# demo_46k22.net
KiCad netlist of a schematic drawn in EAGLE
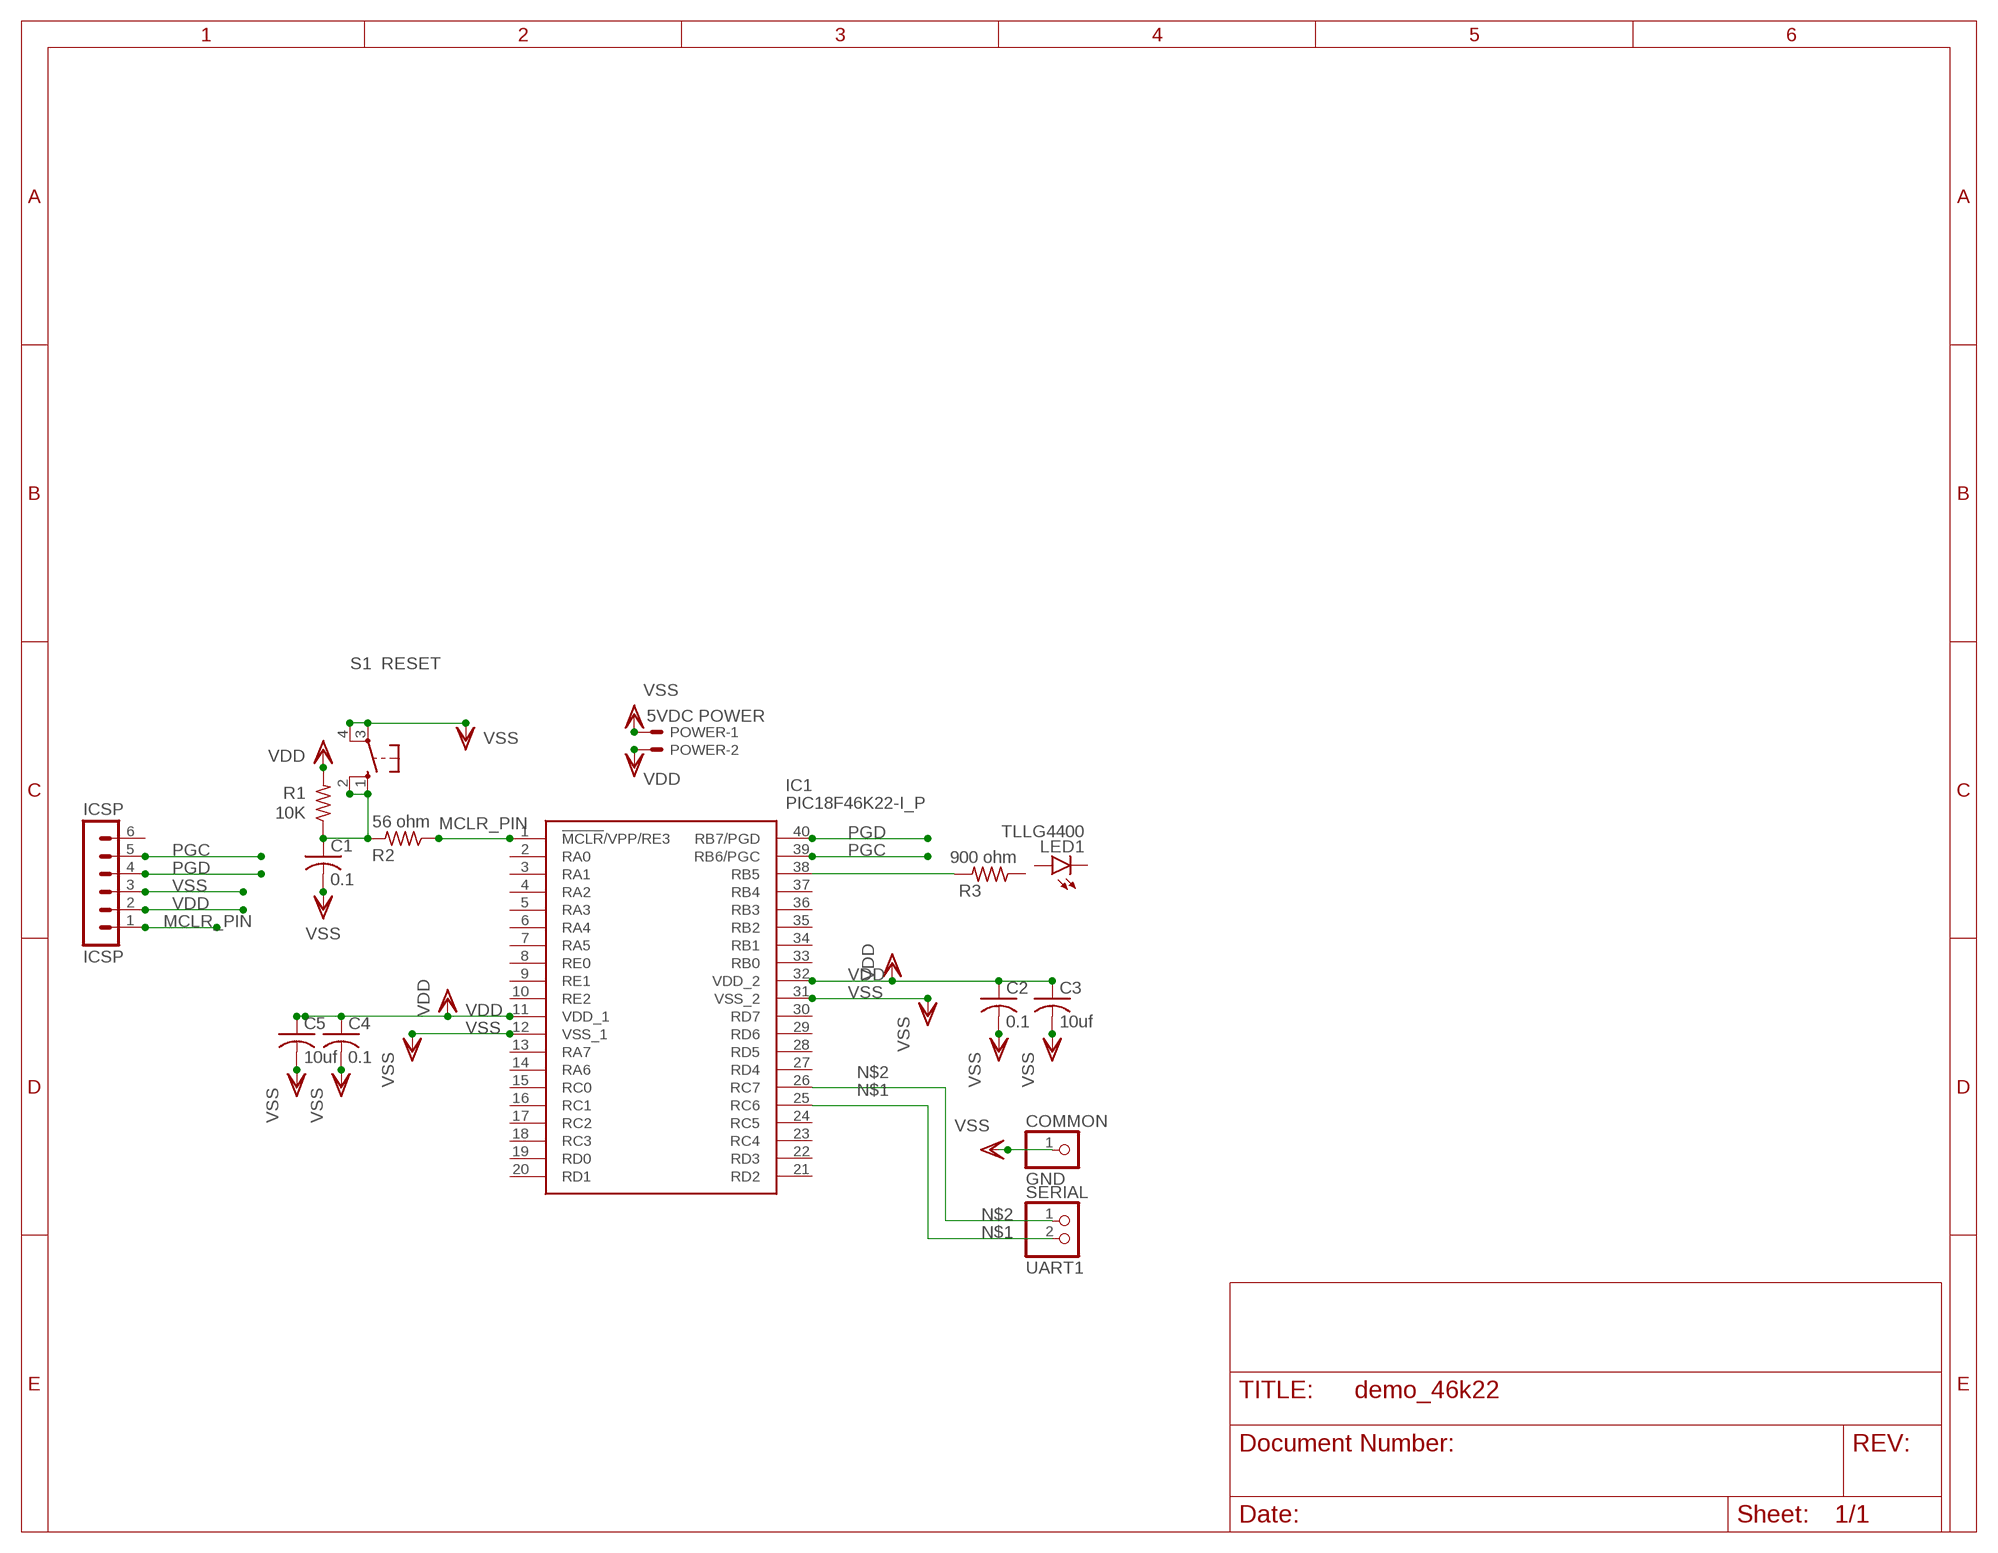
[diagram p0: schematic, sheet 1]

(export (version "E")
  (design (tool "Eeschema 10.0.6"))
  (components
    (comp (ref "C1")
      (value "0.1")
      (footprint "eagle-import:C025-030X050")
      (libsource (lib "eagle-import") (part "C-US025-030X050"))
    )
    (comp (ref "C2")
      (value "0.1")
      (footprint "eagle-import:C025-030X050")
      (libsource (lib "eagle-import") (part "C-US025-030X050"))
    )
    (comp (ref "C3")
      (value "10uf")
      (footprint "eagle-import:C025-030X050")
      (libsource (lib "eagle-import") (part "C-US025-030X050"))
    )
    (comp (ref "C4")
      (value "0.1")
      (footprint "eagle-import:C025-030X050")
      (libsource (lib "eagle-import") (part "C-US025-030X050"))
    )
    (comp (ref "C5")
      (value "10uf")
      (footprint "eagle-import:C025-030X050")
      (libsource (lib "eagle-import") (part "C-US025-030X050"))
    )
    (comp (ref "COMMON")
      (value "GND")
      (footprint "eagle-import:1X01")
      (libsource (lib "eagle-import") (part "PINHD-1X1"))
    )
    (comp (ref "IC1")
      (value "PIC18F46K22-I_P")
      (footprint "eagle-import:DIP1543W58P254L5175H635Q40N")
      (fields
        (field (name "MANUFACTURER_PART_NUMBER") "PIC18F46K22-I/P")
        (field (name "MOUSER_PART_NUMBER") "579-PIC18F46K22IP")
      )
      (libsource (lib "eagle-import") (part "PIC18F46K22-I_P"))
    )
    (comp (ref "ICSP")
      (value "ICSP")
      (footprint "eagle-import:MA06-1")
      (libsource (lib "eagle-import") (part "MA06-1"))
    )
    (comp (ref "LED1")
      (value "TLLG4400")
      (footprint "eagle-import:LED3MM")
      (fields (field (name "MF") "VISHAY SEMICONDUCTOR"))
      (libsource (lib "eagle-import") (part "TLLG4400"))
    )
    (comp (ref "POWER")
      (value "5VDC POWER")
      (footprint "eagle-import:22-23-2021")
      (fields (field (name "MF") "MOLEX") (field (name "MPN") "22-23-2021"))
      (libsource (lib "eagle-import") (part "22-23-2021"))
    )
    (comp (ref "R1")
      (value "10K")
      (footprint "eagle-import:0204_7")
      (libsource (lib "eagle-import") (part "R-US_0204/7"))
    )
    (comp (ref "R2")
      (value "56 ohm")
      (footprint "eagle-import:0204_7")
      (libsource (lib "eagle-import") (part "R-US_0204/7"))
    )
    (comp (ref "R3")
      (value "900 ohm")
      (footprint "eagle-import:0204_7")
      (libsource (lib "eagle-import") (part "R-US_0204/7"))
    )
    (comp (ref "S1")
      (value "RESET")
      (footprint "eagle-import:B3F-10XX")
      (fields (field (name "MPN") "B3F-1000"))
      (libsource (lib "eagle-import") (part "10-XX"))
    )
    (comp (ref "SERIAL")
      (value "UART1")
      (footprint "eagle-import:1X02")
      (libsource (lib "eagle-import") (part "PINHD-1X2"))
    )
  )
  (nets
    (net (code "1") (name "/MCLR_PIN") (class "Default")
      (node (ref "IC1") (pin "1") (pinfunction "~{MCLR}/VPP/RE3_1") (pintype "bidirectional"))
      (node (ref "ICSP") (pin "1") (pinfunction "1_1") (pintype "passive"))
      (node (ref "R2") (pin "1") (pinfunction "1_1") (pintype "passive"))
    )
    (net (code "2") (name "/N$1") (class "Default")
      (node (ref "IC1") (pin "25") (pinfunction "RC6_25") (pintype "bidirectional"))
      (node (ref "SERIAL") (pin "2") (pinfunction "2_2") (pintype "passive"))
    )
    (net (code "3") (name "/N$2") (class "Default")
      (node (ref "IC1") (pin "26") (pinfunction "RC7_26") (pintype "bidirectional"))
      (node (ref "SERIAL") (pin "1") (pinfunction "1_1") (pintype "passive"))
    )
    (net (code "4") (name "/PGC") (class "Default")
      (node (ref "IC1") (pin "39") (pinfunction "RB6/PGC_39") (pintype "bidirectional"))
      (node (ref "ICSP") (pin "5") (pinfunction "5_5") (pintype "passive"))
    )
    (net (code "5") (name "/PGD") (class "Default")
      (node (ref "IC1") (pin "40") (pinfunction "RB7/PGD_40") (pintype "bidirectional"))
      (node (ref "ICSP") (pin "4") (pinfunction "4_4") (pintype "passive"))
    )
    (net (code "6") (name "Net-(IC1-RB5)") (class "Default")
      (node (ref "IC1") (pin "38") (pinfunction "RB5_38") (pintype "bidirectional"))
      (node (ref "R3") (pin "2") (pinfunction "2_2") (pintype "passive"))
    )
    (net (code "7") (name "Net-(S1-S)") (class "Default")
      (node (ref "C1") (pin "1") (pinfunction "1_1") (pintype "passive"))
      (node (ref "R1") (pin "1") (pinfunction "1_1") (pintype "passive"))
      (node (ref "R2") (pin "2") (pinfunction "2_2") (pintype "passive"))
      (node (ref "S1") (pin "1") (pinfunction "S_1") (pintype "passive"))
      (node (ref "S1") (pin "2") (pinfunction "S1_2") (pintype "passive"))
    )
    (net (code "8") (name "VDD") (class "Default")
      (node (ref "C2") (pin "1") (pinfunction "1_1") (pintype "passive"))
      (node (ref "C3") (pin "1") (pinfunction "1_1") (pintype "passive"))
      (node (ref "C4") (pin "1") (pinfunction "1_1") (pintype "passive"))
      (node (ref "C5") (pin "1") (pinfunction "1_1") (pintype "passive"))
      (node (ref "IC1") (pin "11") (pinfunction "VDD_1_11") (pintype "bidirectional"))
      (node (ref "IC1") (pin "32") (pinfunction "VDD_2_32") (pintype "bidirectional"))
      (node (ref "ICSP") (pin "2") (pinfunction "2_2") (pintype "passive"))
      (node (ref "POWER") (pin "2") (pinfunction "S_2") (pintype "passive"))
      (node (ref "R1") (pin "2") (pinfunction "2_2") (pintype "passive"))
    )
    (net (code "9") (name "VSS") (class "Default")
      (node (ref "C1") (pin "2") (pinfunction "2_2") (pintype "passive"))
      (node (ref "C2") (pin "2") (pinfunction "2_2") (pintype "passive"))
      (node (ref "C3") (pin "2") (pinfunction "2_2") (pintype "passive"))
      (node (ref "C4") (pin "2") (pinfunction "2_2") (pintype "passive"))
      (node (ref "C5") (pin "2") (pinfunction "2_2") (pintype "passive"))
      (node (ref "COMMON") (pin "1") (pinfunction "1_1") (pintype "passive"))
      (node (ref "IC1") (pin "12") (pinfunction "VSS_1_12") (pintype "bidirectional"))
      (node (ref "IC1") (pin "31") (pinfunction "VSS_2_31") (pintype "bidirectional"))
      (node (ref "ICSP") (pin "3") (pinfunction "3_3") (pintype "passive"))
      (node (ref "POWER") (pin "1") (pinfunction "S_1") (pintype "passive"))
      (node (ref "S1") (pin "3") (pinfunction "P_3") (pintype "passive"))
      (node (ref "S1") (pin "4") (pinfunction "P1_4") (pintype "passive"))
    )
    (net (code "10") (name "unconnected-(IC1-RA0-Pad2)") (class "Default")
      (node (ref "IC1") (pin "2") (pinfunction "RA0_2") (pintype "bidirectional"))
    )
    (net (code "11") (name "unconnected-(IC1-RA1-Pad3)") (class "Default")
      (node (ref "IC1") (pin "3") (pinfunction "RA1_3") (pintype "bidirectional"))
    )
    (net (code "12") (name "unconnected-(IC1-RA2-Pad4)") (class "Default")
      (node (ref "IC1") (pin "4") (pinfunction "RA2_4") (pintype "bidirectional"))
    )
    (net (code "13") (name "unconnected-(IC1-RA3-Pad5)") (class "Default")
      (node (ref "IC1") (pin "5") (pinfunction "RA3_5") (pintype "bidirectional"))
    )
    (net (code "14") (name "unconnected-(IC1-RA4-Pad6)") (class "Default")
      (node (ref "IC1") (pin "6") (pinfunction "RA4_6") (pintype "bidirectional"))
    )
    (net (code "15") (name "unconnected-(IC1-RA5-Pad7)") (class "Default")
      (node (ref "IC1") (pin "7") (pinfunction "RA5_7") (pintype "bidirectional"))
    )
    (net (code "16") (name "unconnected-(IC1-RA6-Pad14)") (class "Default")
      (node (ref "IC1") (pin "14") (pinfunction "RA6_14") (pintype "bidirectional"))
    )
    (net (code "17") (name "unconnected-(IC1-RA7-Pad13)") (class "Default")
      (node (ref "IC1") (pin "13") (pinfunction "RA7_13") (pintype "bidirectional"))
    )
    (net (code "18") (name "unconnected-(IC1-RB0-Pad33)") (class "Default")
      (node (ref "IC1") (pin "33") (pinfunction "RB0_33") (pintype "bidirectional"))
    )
    (net (code "19") (name "unconnected-(IC1-RB1-Pad34)") (class "Default")
      (node (ref "IC1") (pin "34") (pinfunction "RB1_34") (pintype "bidirectional"))
    )
    (net (code "20") (name "unconnected-(IC1-RB2-Pad35)") (class "Default")
      (node (ref "IC1") (pin "35") (pinfunction "RB2_35") (pintype "bidirectional"))
    )
    (net (code "21") (name "unconnected-(IC1-RB3-Pad36)") (class "Default")
      (node (ref "IC1") (pin "36") (pinfunction "RB3_36") (pintype "bidirectional"))
    )
    (net (code "22") (name "unconnected-(IC1-RB4-Pad37)") (class "Default")
      (node (ref "IC1") (pin "37") (pinfunction "RB4_37") (pintype "bidirectional"))
    )
    (net (code "23") (name "unconnected-(IC1-RC0-Pad15)") (class "Default")
      (node (ref "IC1") (pin "15") (pinfunction "RC0_15") (pintype "bidirectional"))
    )
    (net (code "24") (name "unconnected-(IC1-RC1-Pad16)") (class "Default")
      (node (ref "IC1") (pin "16") (pinfunction "RC1_16") (pintype "bidirectional"))
    )
    (net (code "25") (name "unconnected-(IC1-RC2-Pad17)") (class "Default")
      (node (ref "IC1") (pin "17") (pinfunction "RC2_17") (pintype "bidirectional"))
    )
    (net (code "26") (name "unconnected-(IC1-RC3-Pad18)") (class "Default")
      (node (ref "IC1") (pin "18") (pinfunction "RC3_18") (pintype "bidirectional"))
    )
    (net (code "27") (name "unconnected-(IC1-RC4-Pad23)") (class "Default")
      (node (ref "IC1") (pin "23") (pinfunction "RC4_23") (pintype "bidirectional"))
    )
    (net (code "28") (name "unconnected-(IC1-RC5-Pad24)") (class "Default")
      (node (ref "IC1") (pin "24") (pinfunction "RC5_24") (pintype "bidirectional"))
    )
    (net (code "29") (name "unconnected-(IC1-RD0-Pad19)") (class "Default")
      (node (ref "IC1") (pin "19") (pinfunction "RD0_19") (pintype "bidirectional"))
    )
    (net (code "30") (name "unconnected-(IC1-RD1-Pad20)") (class "Default")
      (node (ref "IC1") (pin "20") (pinfunction "RD1_20") (pintype "bidirectional"))
    )
    (net (code "31") (name "unconnected-(IC1-RD2-Pad21)") (class "Default")
      (node (ref "IC1") (pin "21") (pinfunction "RD2_21") (pintype "bidirectional"))
    )
    (net (code "32") (name "unconnected-(IC1-RD3-Pad22)") (class "Default")
      (node (ref "IC1") (pin "22") (pinfunction "RD3_22") (pintype "bidirectional"))
    )
    (net (code "33") (name "unconnected-(IC1-RD4-Pad27)") (class "Default")
      (node (ref "IC1") (pin "27") (pinfunction "RD4_27") (pintype "bidirectional"))
    )
    (net (code "34") (name "unconnected-(IC1-RD5-Pad28)") (class "Default")
      (node (ref "IC1") (pin "28") (pinfunction "RD5_28") (pintype "bidirectional"))
    )
    (net (code "35") (name "unconnected-(IC1-RD6-Pad29)") (class "Default")
      (node (ref "IC1") (pin "29") (pinfunction "RD6_29") (pintype "bidirectional"))
    )
    (net (code "36") (name "unconnected-(IC1-RD7-Pad30)") (class "Default")
      (node (ref "IC1") (pin "30") (pinfunction "RD7_30") (pintype "bidirectional"))
    )
    (net (code "37") (name "unconnected-(IC1-RE0-Pad8)") (class "Default")
      (node (ref "IC1") (pin "8") (pinfunction "RE0_8") (pintype "bidirectional"))
    )
    (net (code "38") (name "unconnected-(IC1-RE1-Pad9)") (class "Default")
      (node (ref "IC1") (pin "9") (pinfunction "RE1_9") (pintype "bidirectional"))
    )
    (net (code "39") (name "unconnected-(IC1-RE2-Pad10)") (class "Default")
      (node (ref "IC1") (pin "10") (pinfunction "RE2_10") (pintype "bidirectional"))
    )
    (net (code "40") (name "unconnected-(ICSP-Pad6)") (class "Default")
      (node (ref "ICSP") (pin "6") (pinfunction "6_6") (pintype "passive"))
    )
    (net (code "41") (name "unconnected-(LED1-C-PadK)") (class "Default")
      (node (ref "LED1") (pin "K") (pinfunction "C_K") (pintype "passive"))
    )
    (net (code "42") (name "unconnected-(LED1-PadA)") (class "Default")
      (node (ref "LED1") (pin "A") (pinfunction "A_A") (pintype "passive"))
    )
    (net (code "43") (name "unconnected-(R3-Pad1)") (class "Default")
      (node (ref "R3") (pin "1") (pinfunction "1_1") (pintype "passive"))
    )
  )
)
